# ohms-law-1.net
KiCad netlist of a schematic drawn in EAGLE
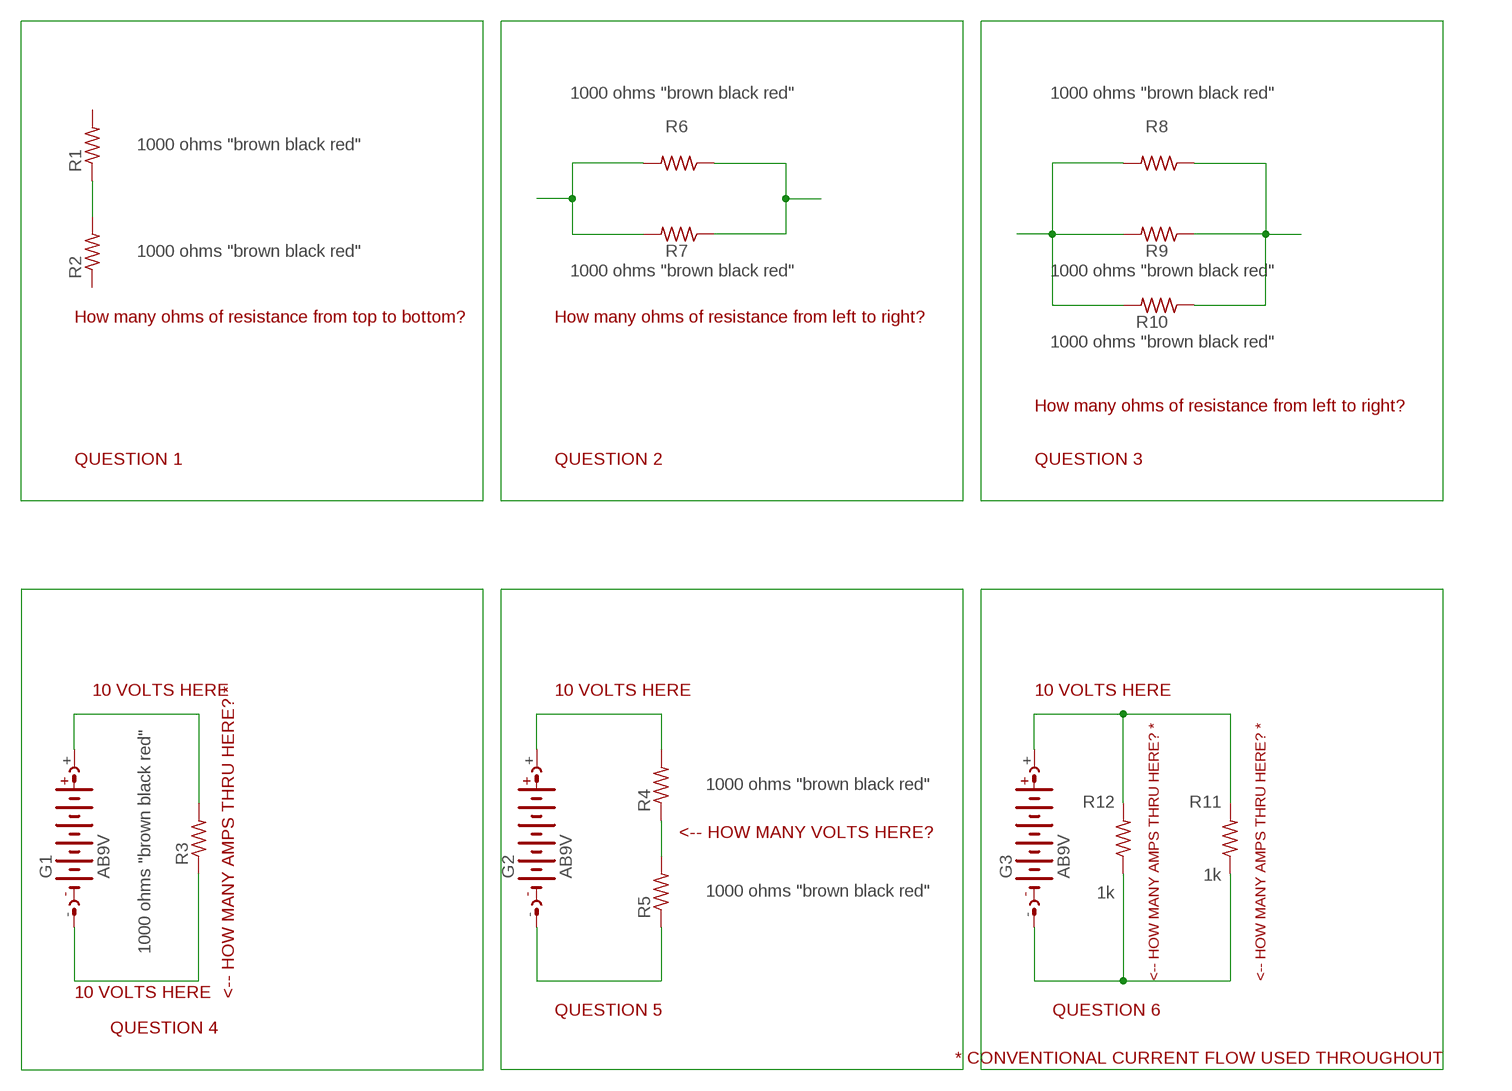
[diagram p0: schematic, sheet 1]

(export (version "E")
  (design (tool "Eeschema 10.0.6"))
  (components
    (comp (ref "G1")
      (value "AB9V")
      (footprint "eagle-import:AB9V")
      (libsource (lib "eagle-import") (part "AB9V"))
    )
    (comp (ref "G2")
      (value "AB9V")
      (footprint "eagle-import:AB9V")
      (libsource (lib "eagle-import") (part "AB9V"))
    )
    (comp (ref "G3")
      (value "AB9V")
      (footprint "eagle-import:AB9V")
      (libsource (lib "eagle-import") (part "AB9V"))
    )
    (comp (ref "R1")
      (value "1000 ohms \"brown black red\"")
      (footprint "eagle-import:M0805")
      (libsource (lib "eagle-import") (part "R-US_M0805"))
    )
    (comp (ref "R2")
      (value "1000 ohms \"brown black red\"")
      (footprint "eagle-import:M0805")
      (libsource (lib "eagle-import") (part "R-US_M0805"))
    )
    (comp (ref "R3")
      (value "1000 ohms \"brown black red\"")
      (footprint "eagle-import:M0805")
      (libsource (lib "eagle-import") (part "R-US_M0805"))
    )
    (comp (ref "R4")
      (value "1000 ohms \"brown black red\"")
      (footprint "eagle-import:M0805")
      (libsource (lib "eagle-import") (part "R-US_M0805"))
    )
    (comp (ref "R5")
      (value "1000 ohms \"brown black red\"")
      (footprint "eagle-import:M0805")
      (libsource (lib "eagle-import") (part "R-US_M0805"))
    )
    (comp (ref "R6")
      (value "1000 ohms \"brown black red\"")
      (footprint "eagle-import:M0805")
      (libsource (lib "eagle-import") (part "R-US_M0805"))
    )
    (comp (ref "R7")
      (value "1000 ohms \"brown black red\"")
      (footprint "eagle-import:M0805")
      (libsource (lib "eagle-import") (part "R-US_M0805"))
    )
    (comp (ref "R8")
      (value "1000 ohms \"brown black red\"")
      (footprint "eagle-import:M0805")
      (libsource (lib "eagle-import") (part "R-US_M0805"))
    )
    (comp (ref "R9")
      (value "1000 ohms \"brown black red\"")
      (footprint "eagle-import:M0805")
      (libsource (lib "eagle-import") (part "R-US_M0805"))
    )
    (comp (ref "R10")
      (value "1000 ohms \"brown black red\"")
      (footprint "eagle-import:M0805")
      (libsource (lib "eagle-import") (part "R-US_M0805"))
    )
    (comp (ref "R11")
      (value "1k")
      (footprint "eagle-import:M0805")
      (libsource (lib "eagle-import") (part "R-US_M0805"))
    )
    (comp (ref "R12")
      (value "1k")
      (footprint "eagle-import:M0805")
      (libsource (lib "eagle-import") (part "R-US_M0805"))
    )
  )
  (nets
    (net (code "4") (name "Net-(G1-Pad+)") (class "Default")
      (node (ref "G1") (pin "+") (pinfunction "+_+") (pintype "passive"))
      (node (ref "R3") (pin "2") (pinfunction "2_2") (pintype "passive"))
    )
    (net (code "5") (name "Net-(G1-Pad-)") (class "Default")
      (node (ref "G1") (pin "-") (pinfunction "-_-") (pintype "passive"))
      (node (ref "R3") (pin "1") (pinfunction "1_1") (pintype "passive"))
    )
    (net (code "6") (name "Net-(G2-Pad+)") (class "Default")
      (node (ref "G2") (pin "+") (pinfunction "+_+") (pintype "passive"))
      (node (ref "R4") (pin "2") (pinfunction "2_2") (pintype "passive"))
    )
    (net (code "7") (name "Net-(G2-Pad-)") (class "Default")
      (node (ref "G2") (pin "-") (pinfunction "-_-") (pintype "passive"))
      (node (ref "R5") (pin "1") (pinfunction "1_1") (pintype "passive"))
    )
    (net (code "8") (name "Net-(G3-Pad+)") (class "Default")
      (node (ref "G3") (pin "+") (pinfunction "+_+") (pintype "passive"))
      (node (ref "R11") (pin "2") (pinfunction "2_2") (pintype "passive"))
      (node (ref "R12") (pin "2") (pinfunction "2_2") (pintype "passive"))
    )
    (net (code "9") (name "Net-(G3-Pad-)") (class "Default")
      (node (ref "G3") (pin "-") (pinfunction "-_-") (pintype "passive"))
      (node (ref "R11") (pin "1") (pinfunction "1_1") (pintype "passive"))
      (node (ref "R12") (pin "1") (pinfunction "1_1") (pintype "passive"))
    )
    (net (code "10") (name "Net-(R1-Pad1)") (class "Default")
      (node (ref "R1") (pin "1") (pinfunction "1_1") (pintype "passive"))
      (node (ref "R2") (pin "2") (pinfunction "2_2") (pintype "passive"))
    )
    (net (code "11") (name "Net-(R4-Pad1)") (class "Default")
      (node (ref "R4") (pin "1") (pinfunction "1_1") (pintype "passive"))
      (node (ref "R5") (pin "2") (pinfunction "2_2") (pintype "passive"))
    )
    (net (code "12") (name "Net-(R6-Pad1)") (class "Default")
      (node (ref "R6") (pin "1") (pinfunction "1_1") (pintype "passive"))
      (node (ref "R7") (pin "1") (pinfunction "1_1") (pintype "passive"))
    )
    (net (code "13") (name "Net-(R6-Pad2)") (class "Default")
      (node (ref "R6") (pin "2") (pinfunction "2_2") (pintype "passive"))
      (node (ref "R7") (pin "2") (pinfunction "2_2") (pintype "passive"))
    )
    (net (code "14") (name "Net-(R10-Pad1)") (class "Default")
      (node (ref "R10") (pin "1") (pinfunction "1_1") (pintype "passive"))
      (node (ref "R8") (pin "1") (pinfunction "1_1") (pintype "passive"))
      (node (ref "R9") (pin "1") (pinfunction "1_1") (pintype "passive"))
    )
    (net (code "15") (name "Net-(R10-Pad2)") (class "Default")
      (node (ref "R10") (pin "2") (pinfunction "2_2") (pintype "passive"))
      (node (ref "R8") (pin "2") (pinfunction "2_2") (pintype "passive"))
      (node (ref "R9") (pin "2") (pinfunction "2_2") (pintype "passive"))
    )
    (net (code "16") (name "unconnected-(R1-Pad2)") (class "Default")
      (node (ref "R1") (pin "2") (pinfunction "2_2") (pintype "passive"))
    )
    (net (code "17") (name "unconnected-(R2-Pad1)") (class "Default")
      (node (ref "R2") (pin "1") (pinfunction "1_1") (pintype "passive"))
    )
  )
)
